# climate_control.net
KiCad netlist of a schematic drawn in EAGLE
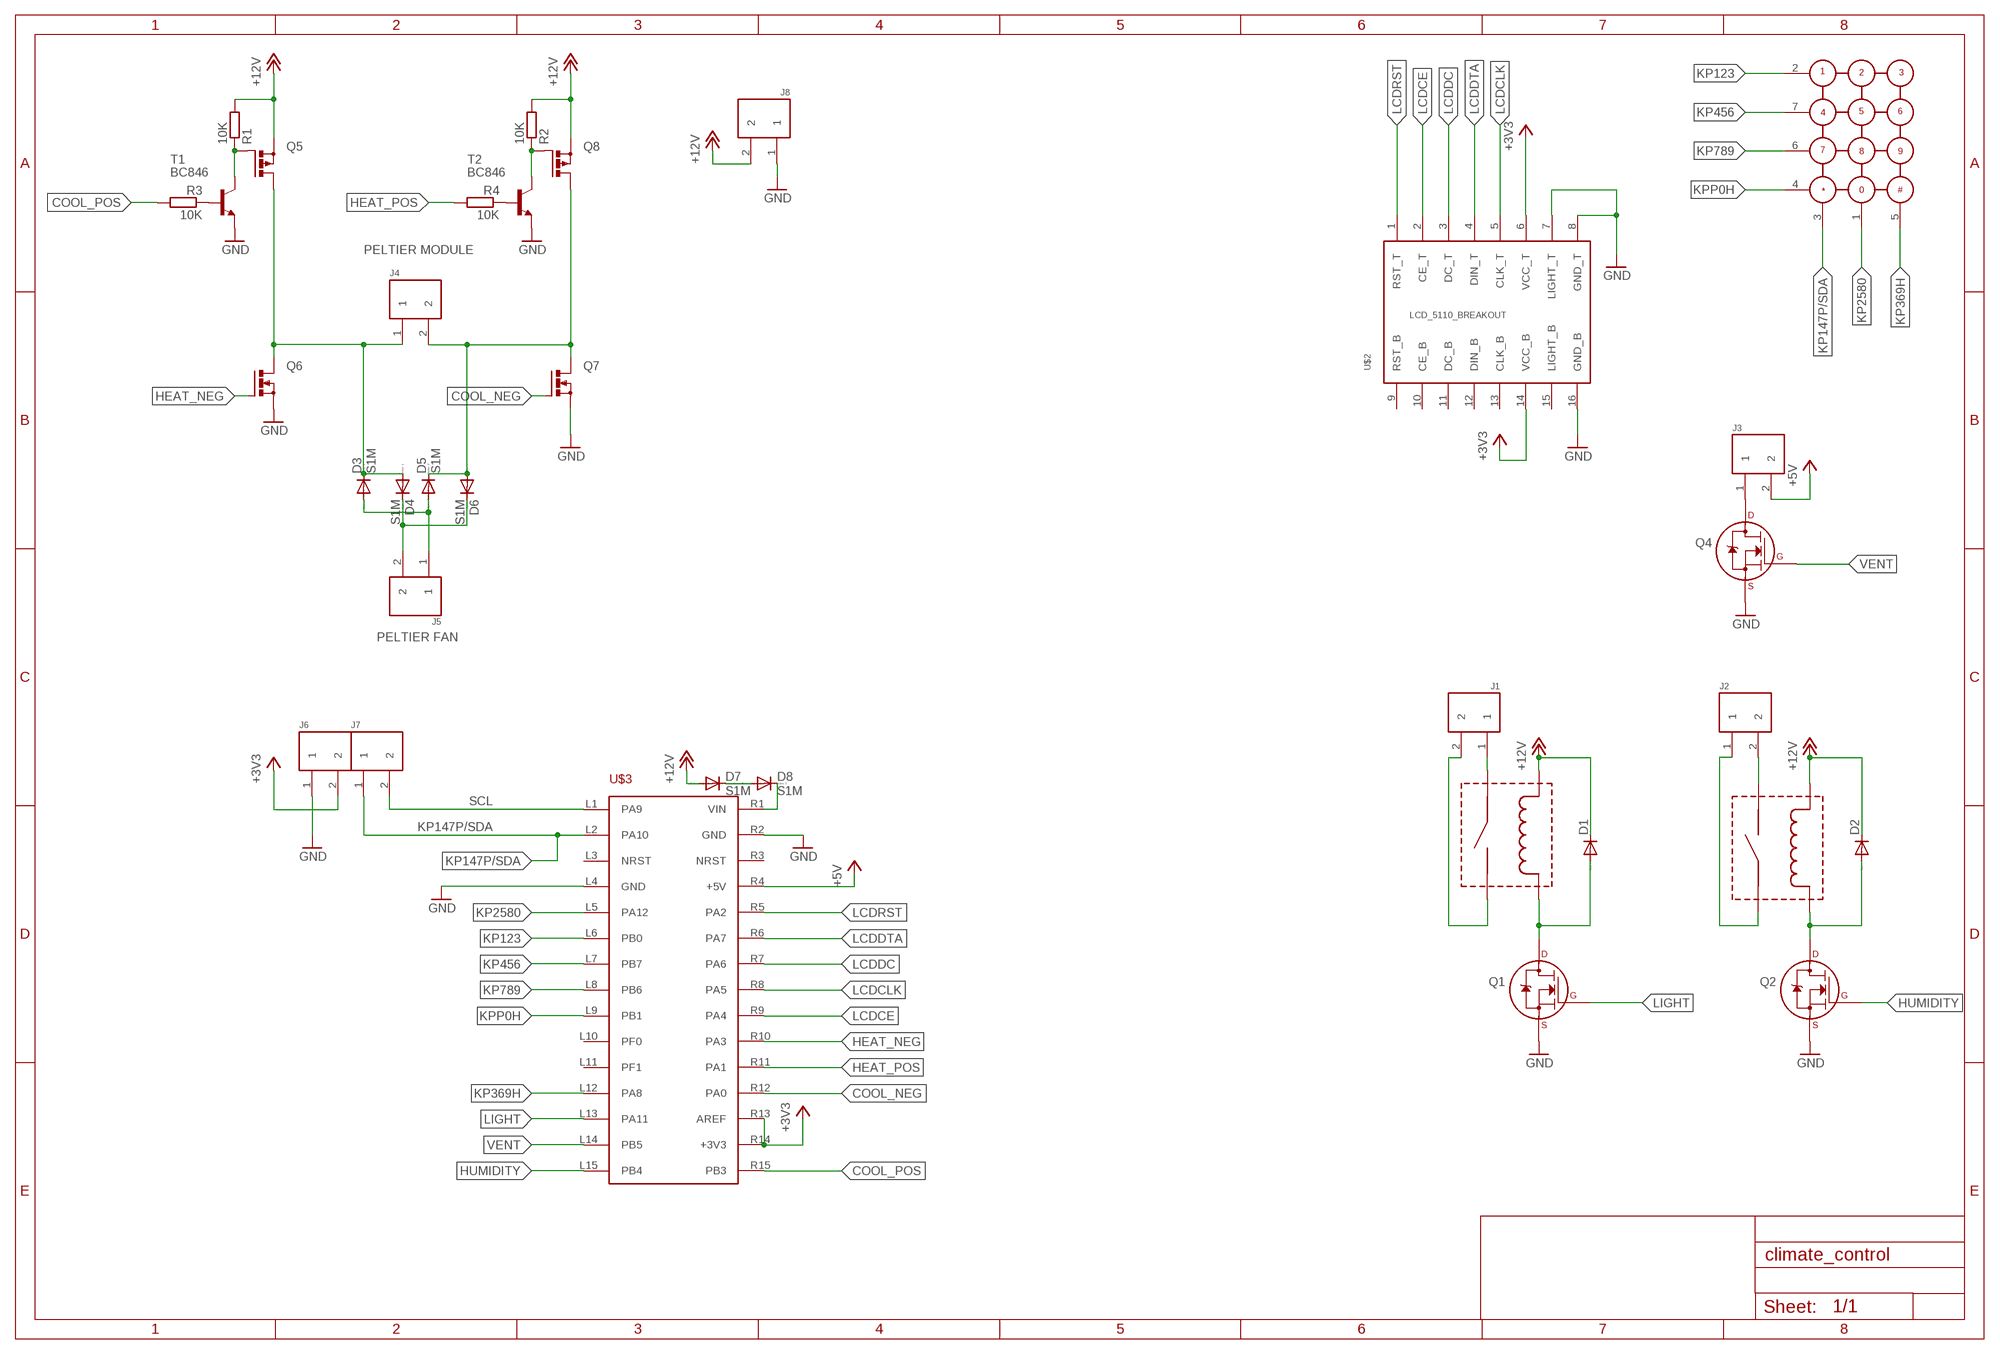
[diagram p0: schematic, sheet 1]

(export (version "E")
  (design (tool "Eeschema 10.0.6"))
  (components
    (comp (ref "D1")
      (value "DIODE-DO-214AC")
      (footprint "eagle-import:DO-214AC")
      (libsource (lib "eagle-import") (part "DIODE-DO-214AC"))
    )
    (comp (ref "D2")
      (value "DIODE-DO-214AC")
      (footprint "eagle-import:DO-214AC")
      (libsource (lib "eagle-import") (part "DIODE-DO-214AC"))
    )
    (comp (ref "D3")
      (value "S1M")
      (footprint "eagle-import:SMA")
      (libsource (lib "eagle-import") (part "S1M"))
    )
    (comp (ref "D4")
      (value "S1M")
      (footprint "eagle-import:SMA")
      (libsource (lib "eagle-import") (part "S1M"))
    )
    (comp (ref "D5")
      (value "S1M")
      (footprint "eagle-import:SMA")
      (libsource (lib "eagle-import") (part "S1M"))
    )
    (comp (ref "D6")
      (value "S1M")
      (footprint "eagle-import:SMA")
      (libsource (lib "eagle-import") (part "S1M"))
    )
    (comp (ref "D7")
      (value "S1M")
      (footprint "eagle-import:SMA")
      (libsource (lib "eagle-import") (part "S1M"))
    )
    (comp (ref "D8")
      (value "S1M")
      (footprint "eagle-import:SMA")
      (libsource (lib "eagle-import") (part "S1M"))
    )
    (comp (ref "J1")
      (value "TERMINAL_PCB_508_X2")
      (footprint "eagle-import:TERMINAL_PCB_508_PITCH")
      (libsource (lib "eagle-import") (part "TERMINAL_PCB_508_X2"))
    )
    (comp (ref "J2")
      (value "TERMINAL_PCB_508_X2")
      (footprint "eagle-import:TERMINAL_PCB_508_PITCH")
      (libsource (lib "eagle-import") (part "TERMINAL_PCB_508_X2"))
    )
    (comp (ref "J3")
      (value "TERMINAL_PCB_508_X2")
      (footprint "eagle-import:TERMINAL_PCB_508_PITCH")
      (libsource (lib "eagle-import") (part "TERMINAL_PCB_508_X2"))
    )
    (comp (ref "J4")
      (value "TERMINAL_PCB_508_X2")
      (footprint "eagle-import:TERMINAL_PCB_508_PITCH")
      (libsource (lib "eagle-import") (part "TERMINAL_PCB_508_X2"))
    )
    (comp (ref "J5")
      (value "TERMINAL_PCB_508_X2")
      (footprint "eagle-import:TERMINAL_PCB_508_PITCH")
      (libsource (lib "eagle-import") (part "TERMINAL_PCB_508_X2"))
    )
    (comp (ref "J6")
      (value "TERMINAL_PCB_508_X2")
      (footprint "eagle-import:TERMINAL_PCB_508_PITCH")
      (libsource (lib "eagle-import") (part "TERMINAL_PCB_508_X2"))
    )
    (comp (ref "J7")
      (value "TERMINAL_PCB_508_X2")
      (footprint "eagle-import:TERMINAL_PCB_508_PITCH")
      (libsource (lib "eagle-import") (part "TERMINAL_PCB_508_X2"))
    )
    (comp (ref "J8")
      (value "TERMINAL_PCB_508_X2")
      (footprint "eagle-import:TERMINAL_PCB_508_PITCH")
      (libsource (lib "eagle-import") (part "TERMINAL_PCB_508_X2"))
    )
    (comp (ref "Q1")
      (value "2N7000_TO92")
      (footprint "eagle-import:TO-92")
      (libsource (lib "eagle-import") (part "2N700_TO920"))
    )
    (comp (ref "Q2")
      (value "2N7000_TO92")
      (footprint "eagle-import:TO-92")
      (libsource (lib "eagle-import") (part "2N700_TO920"))
    )
    (comp (ref "Q4")
      (value "2N7000_TO92")
      (footprint "eagle-import:TO-92")
      (libsource (lib "eagle-import") (part "2N700_TO920"))
    )
    (comp (ref "Q5")
      (value "PMOSFET_PTO220BV")
      (footprint "eagle-import:TO220BV")
      (libsource (lib "eagle-import") (part "PMOSFET_PTO220BV"))
    )
    (comp (ref "Q6")
      (value "PMOSFET_NTO220BV")
      (footprint "eagle-import:TO220BV")
      (libsource (lib "eagle-import") (part "PMOSFET_NTO220BV"))
    )
    (comp (ref "Q7")
      (value "PMOSFET_NTO220BV")
      (footprint "eagle-import:TO220BV")
      (libsource (lib "eagle-import") (part "PMOSFET_NTO220BV"))
    )
    (comp (ref "Q8")
      (value "PMOSFET_PTO220BV")
      (footprint "eagle-import:TO220BV")
      (libsource (lib "eagle-import") (part "PMOSFET_PTO220BV"))
    )
    (comp (ref "R1")
      (value "10K")
      (footprint "eagle-import:R0805")
      (libsource (lib "eagle-import") (part "R-EU_R0805"))
    )
    (comp (ref "R2")
      (value "10K")
      (footprint "eagle-import:R0805")
      (libsource (lib "eagle-import") (part "R-EU_R0805"))
    )
    (comp (ref "R3")
      (value "10K")
      (footprint "eagle-import:R0805")
      (libsource (lib "eagle-import") (part "R-EU_R0805"))
    )
    (comp (ref "R4")
      (value "10K")
      (footprint "eagle-import:R0805")
      (libsource (lib "eagle-import") (part "R-EU_R0805"))
    )
    (comp (ref "T1")
      (value "BC846")
      (footprint "eagle-import:SOT23")
      (libsource (lib "eagle-import") (part "BC846"))
    )
    (comp (ref "T2")
      (value "BC846")
      (footprint "eagle-import:SOT23")
      (libsource (lib "eagle-import") (part "BC846"))
    )
    (comp (ref "U$1")
      (value "KEYPAD12")
      (footprint "eagle-import:KEYPAD12")
      (libsource (lib "eagle-import") (part "KEYPAD12"))
    )
    (comp (ref "U$2")
      (value "LCD_5110_BREAKOUT")
      (footprint "eagle-import:LCD_5110_BREAKOUT")
      (libsource (lib "eagle-import") (part "LCD_5110_BREAKOUT"))
    )
    (comp (ref "U$3")
      (value "NUCLEO_F031")
      (footprint "eagle-import:NUCLEO_30")
      (libsource (lib "eagle-import") (part "NUCLEO_F031"))
    )
    (comp (ref "U$5")
      (value "RELAY_JZC-33F")
      (footprint "eagle-import:RELAY_JZC-33F")
      (libsource (lib "eagle-import") (part "RELAY_JZC-33F"))
    )
    (comp (ref "U$7")
      (value "RELAY_JZC-33F")
      (footprint "eagle-import:RELAY_JZC-33F")
      (libsource (lib "eagle-import") (part "RELAY_JZC-33F"))
    )
  )
  (nets
    (net (code "1") (name "+3V3") (class "Default")
      (node (ref "J6") (pin "2") (pinfunction "2_2") (pintype "bidirectional"))
      (node (ref "U$2") (pin "14") (pinfunction "VCC_B_14") (pintype "power_in"))
      (node (ref "U$2") (pin "6") (pinfunction "VCC_T_6") (pintype "power_in"))
      (node (ref "U$3") (pin "R13") (pinfunction "AREF_R13") (pintype "input"))
      (node (ref "U$3") (pin "R14") (pinfunction "+3V3_R14") (pintype "power_in"))
    )
    (net (code "2") (name "+5V") (class "Default")
      (node (ref "J3") (pin "2") (pinfunction "2_2") (pintype "bidirectional"))
      (node (ref "U$3") (pin "R4") (pinfunction "+5V_R4") (pintype "power_in"))
    )
    (net (code "3") (name "+12V") (class "Default")
      (node (ref "D1") (pin "C") (pinfunction "C_C") (pintype "passive"))
      (node (ref "D2") (pin "C") (pinfunction "C_C") (pintype "passive"))
      (node (ref "D7") (pin "A") (pinfunction "A_A") (pintype "passive"))
      (node (ref "J8") (pin "2") (pinfunction "2_2") (pintype "bidirectional"))
      (node (ref "Q5") (pin "S") (pinfunction "S_S") (pintype "passive"))
      (node (ref "Q8") (pin "S") (pinfunction "S_S") (pintype "passive"))
      (node (ref "R1") (pin "2") (pinfunction "2_2") (pintype "passive"))
      (node (ref "R2") (pin "2") (pinfunction "2_2") (pintype "passive"))
      (node (ref "U$5") (pin "COIL1") (pinfunction "COIL1_COIL1") (pintype "passive"))
      (node (ref "U$7") (pin "COIL2") (pinfunction "COIL2_COIL2") (pintype "passive"))
    )
    (net (code "4") (name "/SCL") (class "Default")
      (node (ref "J7") (pin "2") (pinfunction "2_2") (pintype "bidirectional"))
      (node (ref "U$3") (pin "L1") (pinfunction "PA9_L1") (pintype "bidirectional"))
    )
    (net (code "5") (name "COOL_NEG") (class "Default")
      (node (ref "Q7") (pin "G") (pinfunction "G_G") (pintype "passive"))
      (node (ref "U$3") (pin "R12") (pinfunction "PA0_R12") (pintype "bidirectional"))
    )
    (net (code "6") (name "COOL_POS") (class "Default")
      (node (ref "R3") (pin "2") (pinfunction "2_2") (pintype "passive"))
      (node (ref "U$3") (pin "R15") (pinfunction "PB3_R15") (pintype "bidirectional"))
    )
    (net (code "7") (name "GND") (class "Default")
      (node (ref "J6") (pin "1") (pinfunction "1_1") (pintype "bidirectional"))
      (node (ref "J8") (pin "1") (pinfunction "1_1") (pintype "bidirectional"))
      (node (ref "Q1") (pin "1") (pinfunction "S_1") (pintype "bidirectional"))
      (node (ref "Q2") (pin "1") (pinfunction "S_1") (pintype "bidirectional"))
      (node (ref "Q4") (pin "1") (pinfunction "S_1") (pintype "bidirectional"))
      (node (ref "Q6") (pin "S") (pinfunction "S_S") (pintype "passive"))
      (node (ref "Q7") (pin "S") (pinfunction "S_S") (pintype "passive"))
      (node (ref "T1") (pin "2") (pinfunction "E_2") (pintype "passive"))
      (node (ref "T2") (pin "2") (pinfunction "E_2") (pintype "passive"))
      (node (ref "U$2") (pin "16") (pinfunction "GND_B_16") (pintype "power_in"))
      (node (ref "U$2") (pin "7") (pinfunction "LIGHT_T_7") (pintype "input"))
      (node (ref "U$2") (pin "8") (pinfunction "GND_T_8") (pintype "power_in"))
      (node (ref "U$3") (pin "L4") (pinfunction "GND_L4") (pintype "power_in"))
      (node (ref "U$3") (pin "R2") (pinfunction "GND_R2") (pintype "power_in"))
    )
    (net (code "8") (name "HEAT_NEG") (class "Default")
      (node (ref "Q6") (pin "G") (pinfunction "G_G") (pintype "passive"))
      (node (ref "U$3") (pin "R10") (pinfunction "PA3_R10") (pintype "bidirectional"))
    )
    (net (code "9") (name "HEAT_POS") (class "Default")
      (node (ref "R4") (pin "2") (pinfunction "2_2") (pintype "passive"))
      (node (ref "U$3") (pin "R11") (pinfunction "PA1_R11") (pintype "bidirectional"))
    )
    (net (code "10") (name "HUMIDITY") (class "Default")
      (node (ref "Q2") (pin "2") (pinfunction "G_2") (pintype "tri_state"))
      (node (ref "U$3") (pin "L15") (pinfunction "PB4_L15") (pintype "bidirectional"))
    )
    (net (code "11") (name "KP123") (class "Default")
      (node (ref "U$1") (pin "2") (pinfunction "123_2") (pintype "bidirectional"))
      (node (ref "U$3") (pin "L6") (pinfunction "PB0_L6") (pintype "bidirectional"))
    )
    (net (code "12") (name "KP147P{slash}SDA") (class "Default")
      (node (ref "J7") (pin "1") (pinfunction "1_1") (pintype "bidirectional"))
      (node (ref "U$1") (pin "3") (pinfunction "147*_3") (pintype "bidirectional"))
      (node (ref "U$3") (pin "L2") (pinfunction "PA10_L2") (pintype "bidirectional"))
    )
    (net (code "13") (name "KP369H") (class "Default")
      (node (ref "U$1") (pin "5") (pinfunction "369#_5") (pintype "bidirectional"))
      (node (ref "U$3") (pin "L12") (pinfunction "PA8_L12") (pintype "bidirectional"))
    )
    (net (code "14") (name "KP456") (class "Default")
      (node (ref "U$1") (pin "7") (pinfunction "456_7") (pintype "bidirectional"))
      (node (ref "U$3") (pin "L7") (pinfunction "PB7_L7") (pintype "bidirectional"))
    )
    (net (code "15") (name "KP789") (class "Default")
      (node (ref "U$1") (pin "6") (pinfunction "789_6") (pintype "bidirectional"))
      (node (ref "U$3") (pin "L8") (pinfunction "PB6_L8") (pintype "bidirectional"))
    )
    (net (code "16") (name "KP2580") (class "Default")
      (node (ref "U$1") (pin "1") (pinfunction "2580_1") (pintype "bidirectional"))
      (node (ref "U$3") (pin "L5") (pinfunction "PA12_L5") (pintype "bidirectional"))
    )
    (net (code "17") (name "KPP0H") (class "Default")
      (node (ref "U$1") (pin "4") (pinfunction "*0#_4") (pintype "bidirectional"))
      (node (ref "U$3") (pin "L9") (pinfunction "PB1_L9") (pintype "bidirectional"))
    )
    (net (code "18") (name "LCDCE") (class "Default")
      (node (ref "U$2") (pin "2") (pinfunction "CE_T_2") (pintype "input"))
      (node (ref "U$3") (pin "R9") (pinfunction "PA4_R9") (pintype "bidirectional"))
    )
    (net (code "19") (name "LCDCLK") (class "Default")
      (node (ref "U$2") (pin "5") (pinfunction "CLK_T_5") (pintype "input"))
      (node (ref "U$3") (pin "R8") (pinfunction "PA5_R8") (pintype "bidirectional"))
    )
    (net (code "20") (name "LCDDC") (class "Default")
      (node (ref "U$2") (pin "3") (pinfunction "DC_T_3") (pintype "input"))
      (node (ref "U$3") (pin "R7") (pinfunction "PA6_R7") (pintype "bidirectional"))
    )
    (net (code "21") (name "LCDDTA") (class "Default")
      (node (ref "U$2") (pin "4") (pinfunction "DIN_T_4") (pintype "input"))
      (node (ref "U$3") (pin "R6") (pinfunction "PA7_R6") (pintype "bidirectional"))
    )
    (net (code "22") (name "LCDRST") (class "Default")
      (node (ref "U$2") (pin "1") (pinfunction "RST_T_1") (pintype "input"))
      (node (ref "U$3") (pin "R5") (pinfunction "PA2_R5") (pintype "bidirectional"))
    )
    (net (code "23") (name "LIGHT") (class "Default")
      (node (ref "Q1") (pin "2") (pinfunction "G_2") (pintype "tri_state"))
      (node (ref "U$3") (pin "L13") (pinfunction "PA11_L13") (pintype "bidirectional"))
    )
    (net (code "24") (name "Net-(D3-PadA)") (class "Default")
      (node (ref "D3") (pin "A") (pinfunction "A_A") (pintype "passive"))
      (node (ref "D5") (pin "A") (pinfunction "A_A") (pintype "passive"))
      (node (ref "J5") (pin "1") (pinfunction "1_1") (pintype "bidirectional"))
    )
    (net (code "25") (name "Net-(D3-PadC)") (class "Default")
      (node (ref "D3") (pin "C") (pinfunction "C_C") (pintype "passive"))
      (node (ref "D4") (pin "A") (pinfunction "A_A") (pintype "passive"))
      (node (ref "J4") (pin "1") (pinfunction "1_1") (pintype "bidirectional"))
      (node (ref "Q5") (pin "D") (pinfunction "D_D") (pintype "passive"))
      (node (ref "Q6") (pin "D") (pinfunction "D_D") (pintype "passive"))
    )
    (net (code "26") (name "Net-(D4-PadC)") (class "Default")
      (node (ref "D4") (pin "C") (pinfunction "C_C") (pintype "passive"))
      (node (ref "D6") (pin "C") (pinfunction "C_C") (pintype "passive"))
      (node (ref "J5") (pin "2") (pinfunction "2_2") (pintype "bidirectional"))
    )
    (net (code "27") (name "Net-(D5-PadC)") (class "Default")
      (node (ref "D5") (pin "C") (pinfunction "C_C") (pintype "passive"))
      (node (ref "D6") (pin "A") (pinfunction "A_A") (pintype "passive"))
      (node (ref "J4") (pin "2") (pinfunction "2_2") (pintype "bidirectional"))
      (node (ref "Q7") (pin "D") (pinfunction "D_D") (pintype "passive"))
      (node (ref "Q8") (pin "D") (pinfunction "D_D") (pintype "passive"))
    )
    (net (code "28") (name "Net-(D7-PadC)") (class "Default")
      (node (ref "D7") (pin "C") (pinfunction "C_C") (pintype "passive"))
      (node (ref "D8") (pin "A") (pinfunction "A_A") (pintype "passive"))
    )
    (net (code "29") (name "Net-(J1-Pad1)") (class "Default")
      (node (ref "J1") (pin "1") (pinfunction "1_1") (pintype "bidirectional"))
      (node (ref "U$5") (pin "CONTACT1") (pinfunction "CONTACT1_CONTACT1") (pintype "passive"))
    )
    (net (code "30") (name "Net-(J1-Pad2)") (class "Default")
      (node (ref "J1") (pin "2") (pinfunction "2_2") (pintype "bidirectional"))
      (node (ref "U$5") (pin "CONTACT2") (pinfunction "CONTACT2_CONTACT2") (pintype "passive"))
    )
    (net (code "31") (name "Net-(J2-Pad1)") (class "Default")
      (node (ref "J2") (pin "1") (pinfunction "1_1") (pintype "bidirectional"))
      (node (ref "U$7") (pin "CONTACT1") (pinfunction "CONTACT1_CONTACT1") (pintype "passive"))
    )
    (net (code "32") (name "Net-(J2-Pad2)") (class "Default")
      (node (ref "J2") (pin "2") (pinfunction "2_2") (pintype "bidirectional"))
      (node (ref "U$7") (pin "CONTACT2") (pinfunction "CONTACT2_CONTACT2") (pintype "passive"))
    )
    (net (code "33") (name "Net-(Q1-D)") (class "Default")
      (node (ref "D1") (pin "A") (pinfunction "A_A") (pintype "passive"))
      (node (ref "Q1") (pin "3") (pinfunction "D_3") (pintype "bidirectional"))
      (node (ref "U$5") (pin "COIL2") (pinfunction "COIL2_COIL2") (pintype "passive"))
    )
    (net (code "34") (name "Net-(Q2-D)") (class "Default")
      (node (ref "D2") (pin "A") (pinfunction "A_A") (pintype "passive"))
      (node (ref "Q2") (pin "3") (pinfunction "D_3") (pintype "bidirectional"))
      (node (ref "U$7") (pin "COIL1") (pinfunction "COIL1_COIL1") (pintype "passive"))
    )
    (net (code "35") (name "Net-(Q4-D)") (class "Default")
      (node (ref "J3") (pin "1") (pinfunction "1_1") (pintype "bidirectional"))
      (node (ref "Q4") (pin "3") (pinfunction "D_3") (pintype "bidirectional"))
    )
    (net (code "36") (name "Net-(T1-B)") (class "Default")
      (node (ref "R3") (pin "1") (pinfunction "1_1") (pintype "passive"))
      (node (ref "T1") (pin "1") (pinfunction "B_1") (pintype "passive"))
    )
    (net (code "37") (name "Net-(T1-C)") (class "Default")
      (node (ref "Q5") (pin "G") (pinfunction "G_G") (pintype "passive"))
      (node (ref "R1") (pin "1") (pinfunction "1_1") (pintype "passive"))
      (node (ref "T1") (pin "3") (pinfunction "C_3") (pintype "passive"))
    )
    (net (code "38") (name "Net-(T2-B)") (class "Default")
      (node (ref "R4") (pin "1") (pinfunction "1_1") (pintype "passive"))
      (node (ref "T2") (pin "1") (pinfunction "B_1") (pintype "passive"))
    )
    (net (code "39") (name "Net-(T2-C)") (class "Default")
      (node (ref "Q8") (pin "G") (pinfunction "G_G") (pintype "passive"))
      (node (ref "R2") (pin "1") (pinfunction "1_1") (pintype "passive"))
      (node (ref "T2") (pin "3") (pinfunction "C_3") (pintype "passive"))
    )
    (net (code "40") (name "Net-(U$3-VIN)") (class "Default")
      (node (ref "D8") (pin "C") (pinfunction "C_C") (pintype "passive"))
      (node (ref "U$3") (pin "R1") (pinfunction "VIN_R1") (pintype "power_in"))
    )
    (net (code "41") (name "VENT") (class "Default")
      (node (ref "Q4") (pin "2") (pinfunction "G_2") (pintype "tri_state"))
      (node (ref "U$3") (pin "L14") (pinfunction "PB5_L14") (pintype "bidirectional"))
    )
    (net (code "42") (name "unconnected-(U$2-CE_B-Pad10)") (class "Default")
      (node (ref "U$2") (pin "10") (pinfunction "CE_B_10") (pintype "input"))
    )
    (net (code "43") (name "unconnected-(U$2-CLK_B-Pad13)") (class "Default")
      (node (ref "U$2") (pin "13") (pinfunction "CLK_B_13") (pintype "input"))
    )
    (net (code "44") (name "unconnected-(U$2-DC_B-Pad11)") (class "Default")
      (node (ref "U$2") (pin "11") (pinfunction "DC_B_11") (pintype "input"))
    )
    (net (code "45") (name "unconnected-(U$2-DIN_B-Pad12)") (class "Default")
      (node (ref "U$2") (pin "12") (pinfunction "DIN_B_12") (pintype "input"))
    )
    (net (code "46") (name "unconnected-(U$2-LIGHT_B-Pad15)") (class "Default")
      (node (ref "U$2") (pin "15") (pinfunction "LIGHT_B_15") (pintype "input"))
    )
    (net (code "47") (name "unconnected-(U$2-RST_B-Pad9)") (class "Default")
      (node (ref "U$2") (pin "9") (pinfunction "RST_B_9") (pintype "input"))
    )
    (net (code "48") (name "unconnected-(U$3-NRST-PadL3)") (class "Default")
      (node (ref "U$3") (pin "L3") (pinfunction "NRST_L3") (pintype "input"))
    )
    (net (code "49") (name "unconnected-(U$3-NRST-PadR3)") (class "Default")
      (node (ref "U$3") (pin "R3") (pinfunction "NRST_R3") (pintype "input"))
    )
    (net (code "50") (name "unconnected-(U$3-PF0-PadL10)") (class "Default")
      (node (ref "U$3") (pin "L10") (pinfunction "PF0_L10") (pintype "bidirectional"))
    )
    (net (code "51") (name "unconnected-(U$3-PF1-PadL11)") (class "Default")
      (node (ref "U$3") (pin "L11") (pinfunction "PF1_L11") (pintype "bidirectional"))
    )
  )
)
